# Sheet1.net
KiCad netlist of a schematic drawn in Altium Designer
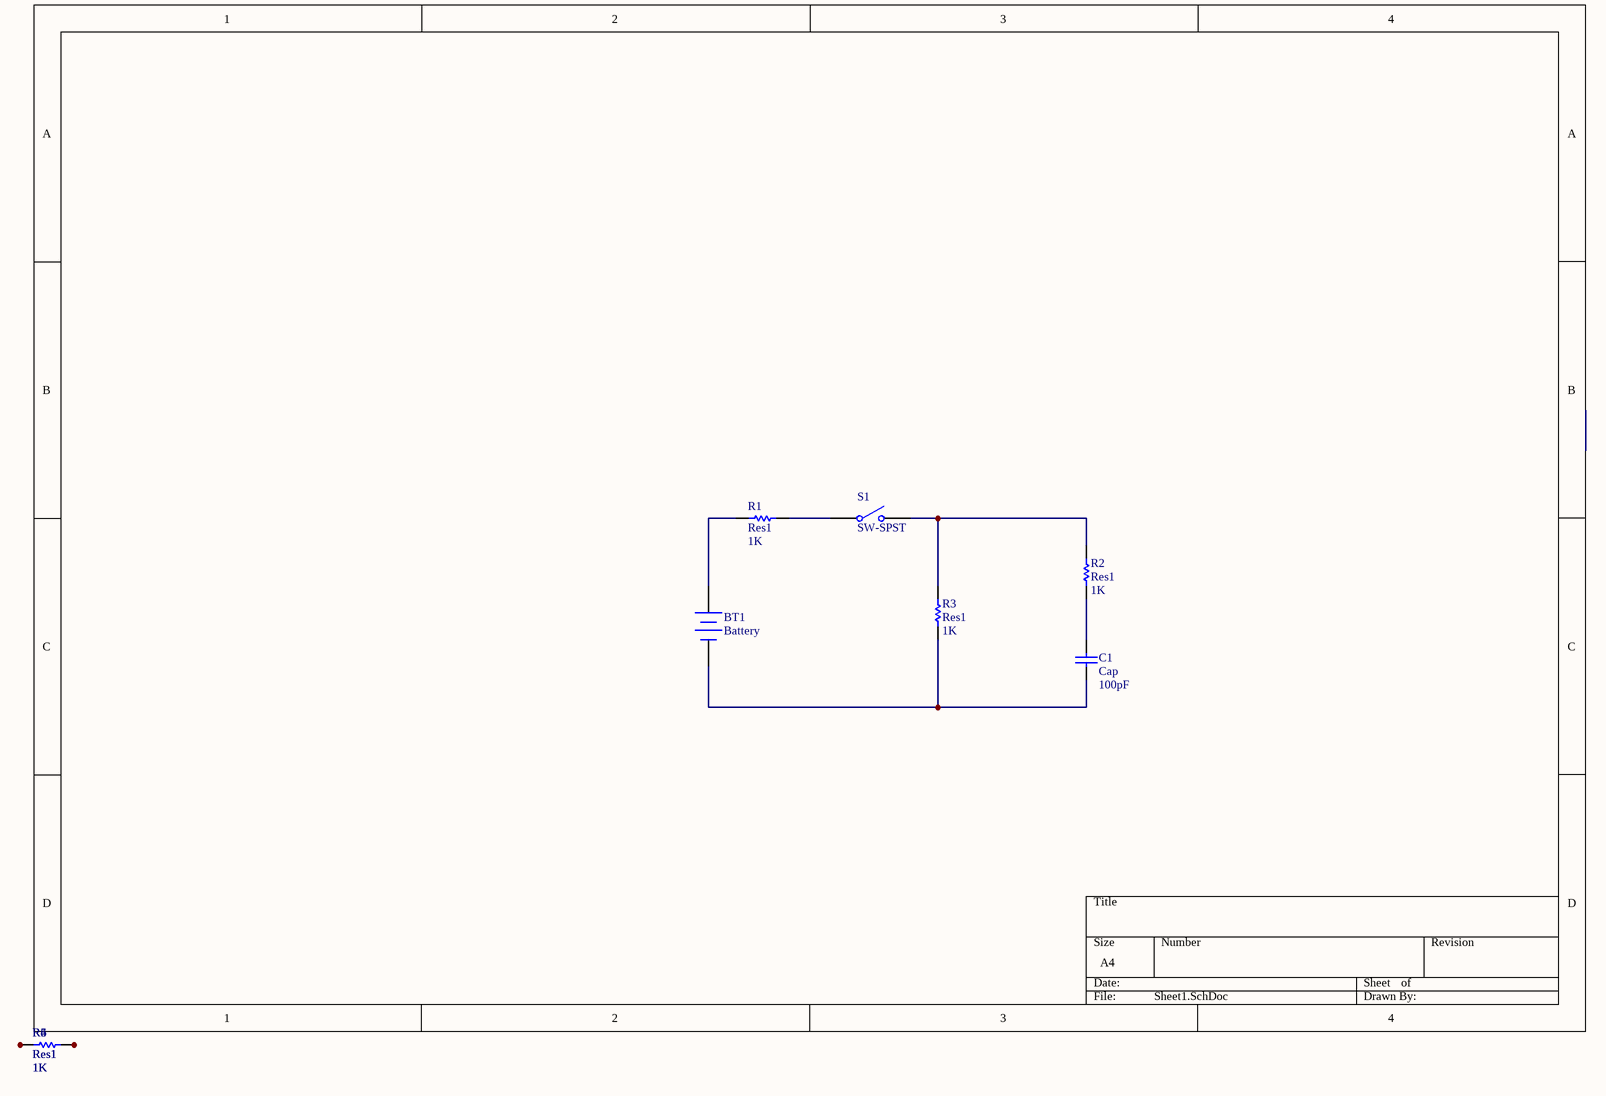
[diagram p0: Sheet1.SchDoc]

(export (version "E")
  (design (tool "Eeschema 10.0.6"))
  (components
    (comp (ref "BT1")
      (value "Battery")
      (footprint "BAT-2")
      (description "Multicell Battery")
      (fields (field (name "PUBLISHER") "Altium Limited"))
      (libsource (lib "Miscellaneous Devices") (part "Battery"))
    )
    (comp (ref "C1")
      (value "Cap")
      (footprint "RAD-0.3")
      (description "Capacitor")
      (fields (field (name "ALTIUM_VALUE") "100pF") (field (name "PUBLISHER") "Altium Limited"))
      (libsource (lib "Miscellaneous Devices") (part "Cap"))
    )
    (comp (ref "R1")
      (value "Res1")
      (footprint "AXIAL-0.3")
      (description "Resistor")
      (fields (field (name "ALTIUM_VALUE") "1K") (field (name "PUBLISHER") "Altium Limited"))
      (libsource (lib "Miscellaneous Devices") (part "Res1"))
    )
    (comp (ref "R2")
      (value "Res1")
      (footprint "AXIAL-0.3")
      (description "Resistor")
      (fields (field (name "ALTIUM_VALUE") "1K") (field (name "PUBLISHER") "Altium Limited"))
      (libsource (lib "Miscellaneous Devices") (part "Res1"))
    )
    (comp (ref "R3")
      (value "Res1")
      (footprint "AXIAL-0.3")
      (description "Resistor")
      (fields (field (name "ALTIUM_VALUE") "1K") (field (name "PUBLISHER") "Altium Limited"))
      (libsource (lib "Miscellaneous Devices") (part "Res1"))
    )
    (comp (ref "R4")
      (value "Res1")
      (footprint "AXIAL-0.3")
      (description "Resistor")
      (fields (field (name "ALTIUM_VALUE") "1K") (field (name "PUBLISHER") "Altium Limited"))
      (libsource (lib "Miscellaneous Devices") (part "Res1"))
    )
    (comp (ref "R5")
      (value "Res1")
      (footprint "AXIAL-0.3")
      (description "Resistor")
      (fields (field (name "ALTIUM_VALUE") "1K") (field (name "PUBLISHER") "Altium Limited"))
      (libsource (lib "Miscellaneous Devices") (part "Res1"))
    )
    (comp (ref "R6")
      (value "Res1")
      (footprint "AXIAL-0.3")
      (description "Resistor")
      (fields (field (name "ALTIUM_VALUE") "1K") (field (name "PUBLISHER") "Altium Limited"))
      (libsource (lib "Miscellaneous Devices") (part "Res1"))
    )
    (comp (ref "S1")
      (value "SW-SPST")
      (footprint "SPST-2")
      (description "Single-Pole, Single-Throw Switch")
      (fields (field (name "PUBLISHER") "Altium Limited"))
      (libsource (lib "Miscellaneous Devices") (part "SW-SPST"))
    )
  )
  (nets
    (net (code "1") (name "Net-(BT1-+)") (class "Default")
      (node (ref "BT1") (pin "1") (pinfunction "+_1") (pintype "passive"))
      (node (ref "R1") (pin "1") (pinfunction "1_1") (pintype "passive"))
    )
    (net (code "2") (name "Net-(BT1--)") (class "Default")
      (node (ref "BT1") (pin "2") (pinfunction "-_2") (pintype "passive"))
      (node (ref "C1") (pin "1") (pinfunction "1_1") (pintype "passive"))
      (node (ref "R3") (pin "1") (pinfunction "1_1") (pintype "passive"))
    )
    (net (code "3") (name "Net-(C1-Pad2)") (class "Default")
      (node (ref "C1") (pin "2") (pinfunction "2_2") (pintype "passive"))
      (node (ref "R2") (pin "1") (pinfunction "1_1") (pintype "passive"))
    )
    (net (code "4") (name "Net-(R4-Pad1)") (class "Default")
      (node (ref "R4") (pin "1") (pinfunction "1_1") (pintype "passive"))
      (node (ref "R5") (pin "1") (pinfunction "1_1") (pintype "passive"))
      (node (ref "R6") (pin "1") (pinfunction "1_1") (pintype "passive"))
    )
    (net (code "5") (name "Net-(R4-Pad2)") (class "Default")
      (node (ref "R4") (pin "2") (pinfunction "2_2") (pintype "passive"))
      (node (ref "R5") (pin "2") (pinfunction "2_2") (pintype "passive"))
      (node (ref "R6") (pin "2") (pinfunction "2_2") (pintype "passive"))
    )
    (net (code "6") (name "Net-(S1-COMMON)") (class "Default")
      (node (ref "R1") (pin "2") (pinfunction "2_2") (pintype "passive"))
      (node (ref "S1") (pin "1") (pinfunction "COMMON_1") (pintype "passive"))
    )
    (net (code "7") (name "Net-(S1-NO)") (class "Default")
      (node (ref "R2") (pin "2") (pinfunction "2_2") (pintype "passive"))
      (node (ref "R3") (pin "2") (pinfunction "2_2") (pintype "passive"))
      (node (ref "S1") (pin "2") (pinfunction "NO_2") (pintype "passive"))
    )
  )
)
